# PowerConnector.net
KiCad netlist of a schematic drawn in Altium Designer
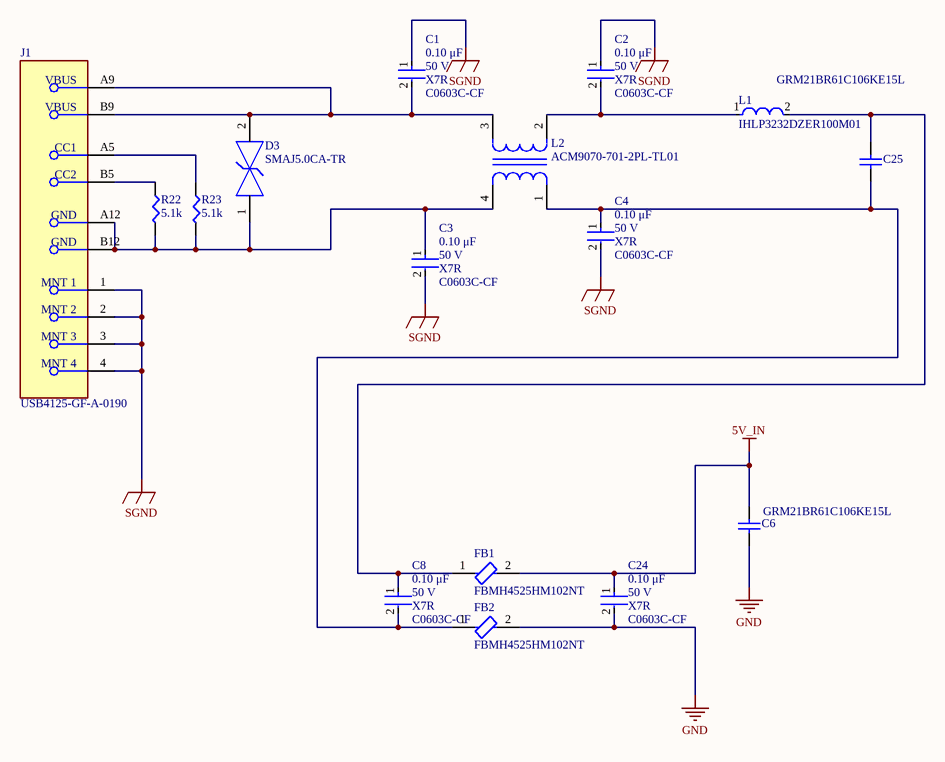
[diagram p0: PowerConnector.SchDoc]

(export (version "E")
  (design (tool "Eeschema 10.0.6"))
  (components
    (comp (ref "C1")
      (value "0.10 μF")
      (footprint "FP-C0603C-CF-MFG")
      (description "CAP CER 0.1UF 50V X7R 0603")
      (fields
        (field (name "TOLERANCE") "0.1")
        (field (name "MANUFACTURER") "KEMET")
        (field (name "PACKAGE") "C0603C-CF")
        (field (name "VOLTAGE RATING") "50 V")
        (field (name "TEMPERATURE CHARACTERISTIC") "X7R")
      )
      (libsource (lib "Altium Content Vault") (part "b4654b650e69147ec39a6b967a45e02"))
    )
    (comp (ref "C2")
      (value "0.10 μF")
      (footprint "FP-C0603C-CF-MFG")
      (description "CAP CER 0.1UF 50V X7R 0603")
      (fields
        (field (name "TOLERANCE") "0.1")
        (field (name "MANUFACTURER") "KEMET")
        (field (name "PACKAGE") "C0603C-CF")
        (field (name "VOLTAGE RATING") "50 V")
        (field (name "TEMPERATURE CHARACTERISTIC") "X7R")
      )
      (libsource (lib "Altium Content Vault") (part "b4654b650e69147ec39a6b967a45e02"))
    )
    (comp (ref "C3")
      (value "0.10 μF")
      (footprint "FP-C0603C-CF-MFG")
      (description "CAP CER 0.1UF 50V X7R 0603")
      (fields
        (field (name "TOLERANCE") "0.1")
        (field (name "MANUFACTURER") "KEMET")
        (field (name "PACKAGE") "C0603C-CF")
        (field (name "VOLTAGE RATING") "50 V")
        (field (name "TEMPERATURE CHARACTERISTIC") "X7R")
      )
      (libsource (lib "Altium Content Vault") (part "b4654b650e69147ec39a6b967a45e02"))
    )
    (comp (ref "C4")
      (value "0.10 μF")
      (footprint "FP-C0603C-CF-MFG")
      (description "CAP CER 0.1UF 50V X7R 0603")
      (fields
        (field (name "TOLERANCE") "0.1")
        (field (name "MANUFACTURER") "KEMET")
        (field (name "PACKAGE") "C0603C-CF")
        (field (name "VOLTAGE RATING") "50 V")
        (field (name "TEMPERATURE CHARACTERISTIC") "X7R")
      )
      (libsource (lib "Altium Content Vault") (part "b4654b650e69147ec39a6b967a45e02"))
    )
    (comp (ref "C6")
      (value "GRM21BR61C106KE15L")
      (footprint "CAPC2013X135X50LL10T20")
      (fields (field (name "MANUFACTURER") "Murata"))
      (libsource (lib "Altium Content Vault") (part "CAP"))
    )
    (comp (ref "C8")
      (value "0.10 μF")
      (footprint "FP-C0603C-CF-MFG")
      (description "CAP CER 0.1UF 50V X7R 0603")
      (fields
        (field (name "TOLERANCE") "0.1")
        (field (name "MANUFACTURER") "KEMET")
        (field (name "PACKAGE") "C0603C-CF")
        (field (name "VOLTAGE RATING") "50 V")
        (field (name "TEMPERATURE CHARACTERISTIC") "X7R")
      )
      (libsource (lib "Altium Content Vault") (part "b4654b650e69147ec39a6b967a45e02"))
    )
    (comp (ref "C24")
      (value "0.10 μF")
      (footprint "FP-C0603C-CF-MFG")
      (description "CAP CER 0.1UF 50V X7R 0603")
      (fields
        (field (name "TOLERANCE") "0.1")
        (field (name "MANUFACTURER") "KEMET")
        (field (name "PACKAGE") "C0603C-CF")
        (field (name "VOLTAGE RATING") "50 V")
        (field (name "TEMPERATURE CHARACTERISTIC") "X7R")
      )
      (libsource (lib "Altium Content Vault") (part "b4654b650e69147ec39a6b967a45e02"))
    )
    (comp (ref "C25")
      (value "GRM21BR61C106KE15L")
      (footprint "CAPC2013X135X50LL10T20")
      (fields (field (name "MANUFACTURER") "Murata"))
      (libsource (lib "Altium Content Vault") (part "CAP"))
    )
    (comp (ref "D3")
      (value "SMAJ5.0CA-TR")
      (footprint "FP-SMA-MFG")
      (description "TVS DIODE 5V 13.4V SMA")
      (fields
        (field (name "MANUFACTURER") "STMicroelectronics")
        (field (name "OCTOPART") "https://octopart.com/smaj5.0ca-tr-stmicroelectronics-350177")
      )
      (libsource (lib "Altium Content Vault") (part "876f4347bf90aa6f500f43e3cd03972"))
    )
    (comp (ref "FB1")
      (value "FBMH4525HM102NT")
      (footprint "FP-FBMH4525-MFG")
      (description "FERRITE BEAD 1 KOHM 1810 1LN")
      (fields (field (name "MANUFACTURER") "Taiyo Yuden") (field (name "TOLERANCE") "30%"))
      (libsource (lib "Altium Content Vault") (part "5f30dd21d616792df468990f7003faa"))
    )
    (comp (ref "FB2")
      (value "FBMH4525HM102NT")
      (footprint "FP-FBMH4525-MFG")
      (description "FERRITE BEAD 1 KOHM 1810 1LN")
      (fields (field (name "MANUFACTURER") "Taiyo Yuden") (field (name "TOLERANCE") "30%"))
      (libsource (lib "Altium Content Vault") (part "5f30dd21d616792df468990f7003faa"))
    )
    (comp (ref "J1")
      (value "USB4125-GF-A-0190")
      (footprint "FP-USB4125-GF-A-0190-MFG")
      (description "CONN RCPT TYPE C 6P SMD RA")
      (libsource (lib "Altium Content Vault") (part "a055484d46e58b234844902c9fd883a"))
    )
    (comp (ref "L1")
      (value "IHLP3232DZER100M01")
      (footprint "FP-IHLP-3232DZ-FP_2_413x5-MFG")
      (description "FIXED IND 10UH 5.2A 59.9 MOHM")
      (fields (field (name "TOLERANCE") "20%"))
      (libsource (lib "Altium Content Vault") (part "725321dda6339637d4d059423bc1c3c"))
    )
    (comp (ref "L2")
      (value "ACM9070-701-2PL-TL01")
      (footprint "FP-ACM9070-MFG")
      (description "CMC 5A 2LN 700 OHM SMD")
      (libsource (lib "Altium Content Vault") (part "ab69b6302e6ba7bc51d6eec5c8e52de"))
    )
    (comp (ref "R22")
      (value "5.1k")
      (footprint "SMD-0603-RES")
      (description "RES SMD 5.1K OHM 1% 1/10W 0603")
      (fields
        (field (name "PART NUMBER") "ERJ-3EKF5101V")
        (field (name "DIGI-KEY PART NUMBER") "P5.10KHCT-ND")
      )
      (libsource (lib "Panasonic_ERJ_0603") (part "ERJ-3EKF5101V"))
    )
    (comp (ref "R23")
      (value "5.1k")
      (footprint "SMD-0603-RES")
      (description "RES SMD 5.1K OHM 1% 1/10W 0603")
      (fields
        (field (name "PART NUMBER") "ERJ-3EKF5101V")
        (field (name "DIGI-KEY PART NUMBER") "P5.10KHCT-ND")
      )
      (libsource (lib "Panasonic_ERJ_0603") (part "ERJ-3EKF5101V"))
    )
  )
  (nets
    (net (code "1") (name "5V_IN") (class "Default")
      (node (ref "C24") (pin "1") (pinfunction "1_1") (pintype "passive"))
      (node (ref "C6") (pin "2") (pinfunction "2_2") (pintype "passive"))
      (node (ref "FB1") (pin "2") (pinfunction "2_2") (pintype "passive"))
    )
    (net (code "2") (name "GND") (class "Default")
      (node (ref "C24") (pin "2") (pinfunction "2_2") (pintype "passive"))
      (node (ref "C6") (pin "1") (pinfunction "1_1") (pintype "passive"))
      (node (ref "FB2") (pin "2") (pinfunction "2_2") (pintype "passive"))
    )
    (net (code "3") (name "Net-(C1-Pad2)") (class "Default")
      (node (ref "C1") (pin "2") (pinfunction "2_2") (pintype "passive"))
      (node (ref "D3") (pin "2") (pinfunction "2_2") (pintype "passive"))
      (node (ref "J1") (pin "A9") (pinfunction "VBUS_A9") (pintype "passive"))
      (node (ref "J1") (pin "B9") (pinfunction "VBUS_B9") (pintype "passive"))
      (node (ref "L2") (pin "3") (pinfunction "3_3") (pintype "passive"))
    )
    (net (code "4") (name "Net-(C2-Pad2)") (class "Default")
      (node (ref "C2") (pin "2") (pinfunction "2_2") (pintype "passive"))
      (node (ref "L1") (pin "1") (pinfunction "1_1") (pintype "passive"))
      (node (ref "L2") (pin "2") (pinfunction "2_2") (pintype "passive"))
    )
    (net (code "5") (name "Net-(C3-Pad1)") (class "Default")
      (node (ref "C3") (pin "1") (pinfunction "1_1") (pintype "passive"))
      (node (ref "D3") (pin "1") (pinfunction "1_1") (pintype "passive"))
      (node (ref "J1") (pin "A12") (pinfunction "GND_A12") (pintype "passive"))
      (node (ref "J1") (pin "B12") (pinfunction "GND_B12") (pintype "passive"))
      (node (ref "L2") (pin "4") (pinfunction "4_4") (pintype "passive"))
      (node (ref "R22") (pin "2") (pinfunction "2_2") (pintype "passive"))
      (node (ref "R23") (pin "2") (pinfunction "2_2") (pintype "passive"))
    )
    (net (code "6") (name "Net-(C25-Pad1)") (class "Default")
      (node (ref "C25") (pin "1") (pinfunction "1_1") (pintype "passive"))
      (node (ref "C4") (pin "1") (pinfunction "1_1") (pintype "passive"))
      (node (ref "C8") (pin "2") (pinfunction "2_2") (pintype "passive"))
      (node (ref "FB2") (pin "1") (pinfunction "1_1") (pintype "passive"))
      (node (ref "L2") (pin "1") (pinfunction "1_1") (pintype "passive"))
    )
    (net (code "7") (name "Net-(C25-Pad2)") (class "Default")
      (node (ref "C25") (pin "2") (pinfunction "2_2") (pintype "passive"))
      (node (ref "C8") (pin "1") (pinfunction "1_1") (pintype "passive"))
      (node (ref "FB1") (pin "1") (pinfunction "1_1") (pintype "passive"))
      (node (ref "L1") (pin "2") (pinfunction "2_2") (pintype "passive"))
    )
    (net (code "8") (name "Net-(J1-CC1)") (class "Default")
      (node (ref "J1") (pin "A5") (pinfunction "CC1_A5") (pintype "passive"))
      (node (ref "R23") (pin "1") (pinfunction "1_1") (pintype "passive"))
    )
    (net (code "9") (name "Net-(J1-CC2)") (class "Default")
      (node (ref "J1") (pin "B5") (pinfunction "CC2_B5") (pintype "passive"))
      (node (ref "R22") (pin "1") (pinfunction "1_1") (pintype "passive"))
    )
    (net (code "10") (name "SGND") (class "Default")
      (node (ref "C1") (pin "1") (pinfunction "1_1") (pintype "passive"))
      (node (ref "C2") (pin "1") (pinfunction "1_1") (pintype "passive"))
      (node (ref "C3") (pin "2") (pinfunction "2_2") (pintype "passive"))
      (node (ref "C4") (pin "2") (pinfunction "2_2") (pintype "passive"))
      (node (ref "J1") (pin "1") (pinfunction "MNT_1_1") (pintype "passive"))
      (node (ref "J1") (pin "2") (pinfunction "MNT_2_2") (pintype "passive"))
      (node (ref "J1") (pin "3") (pinfunction "MNT_3_3") (pintype "passive"))
      (node (ref "J1") (pin "4") (pinfunction "MNT_4_4") (pintype "passive"))
    )
  )
)
